# Stepper_Motor_Driver.net
KiCad netlist of a schematic drawn in EAGLE
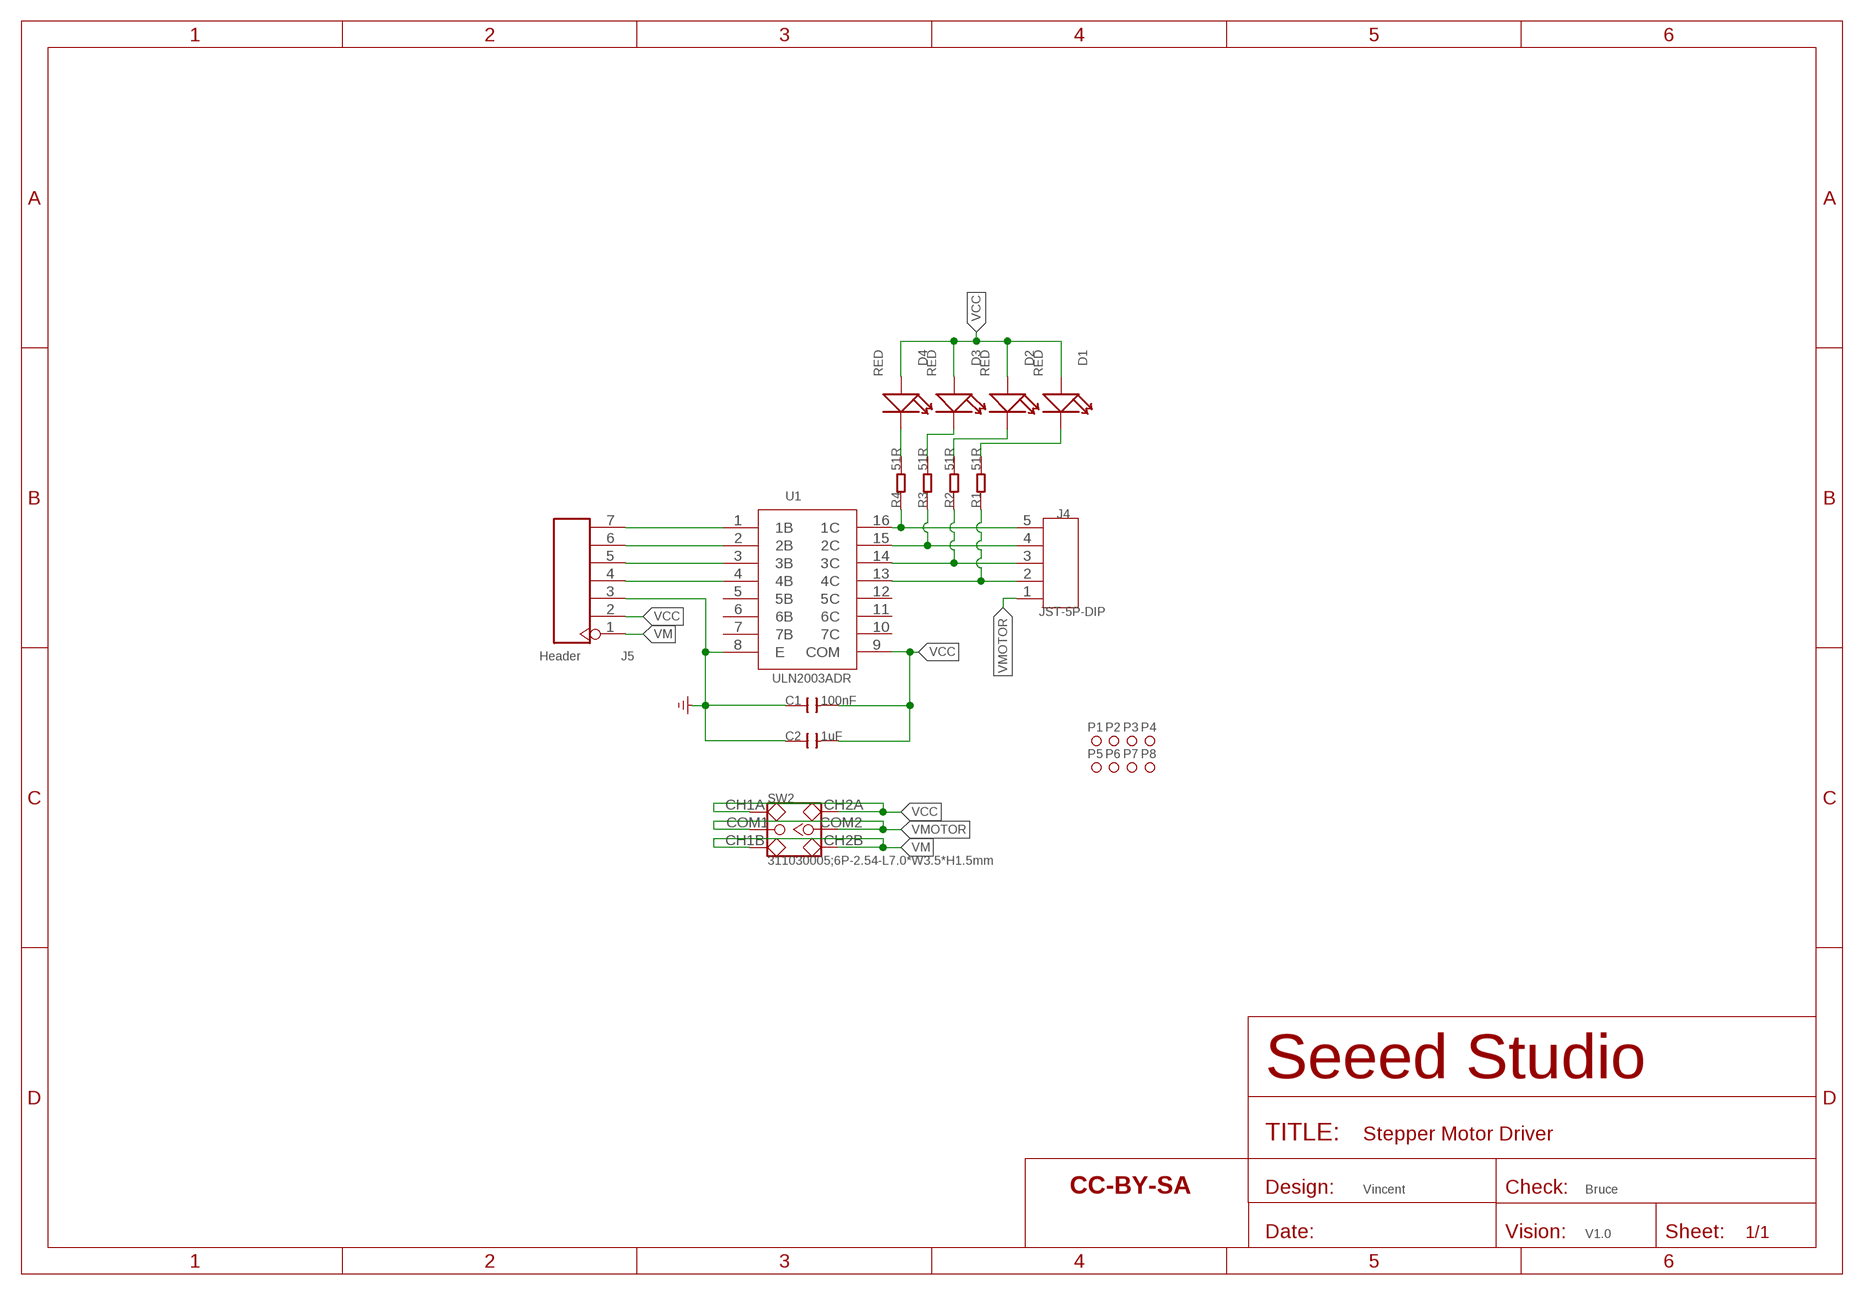
[diagram p0: schematic, sheet 1]

(export (version "E")
  (design (tool "Eeschema 10.0.6"))
  (components
    (comp (ref "C1")
      (value "100nF")
      (footprint "eagle-import:C0603")
      (libsource (lib "eagle-import") (part "CAP-0603"))
    )
    (comp (ref "C2")
      (value "1uF")
      (footprint "eagle-import:C0603")
      (libsource (lib "eagle-import") (part "CAP-0603"))
    )
    (comp (ref "D1")
      (value "RED")
      (footprint "eagle-import:LED-0603")
      (libsource (lib "eagle-import") (part "LED'0603'"))
    )
    (comp (ref "D2")
      (value "RED")
      (footprint "eagle-import:LED-0603")
      (libsource (lib "eagle-import") (part "LED'0603'"))
    )
    (comp (ref "D3")
      (value "RED")
      (footprint "eagle-import:LED-0603")
      (libsource (lib "eagle-import") (part "LED'0603'"))
    )
    (comp (ref "D4")
      (value "RED")
      (footprint "eagle-import:LED-0603")
      (libsource (lib "eagle-import") (part "LED'0603'"))
    )
    (comp (ref "J4")
      (value "JST-5P-DIP")
      (footprint "eagle-import:JST5-2.54")
      (libsource (lib "eagle-import") (part "JST-5P-DIP"))
    )
    (comp (ref "J5")
      (value "Header")
      (footprint "eagle-import:H7-2.54")
      (libsource (lib "eagle-import") (part "HEADER-7P"))
    )
    (comp (ref "P1")
      (value "MARK-1.0'ANNULAR'")
      (footprint "eagle-import:ROUND-MARK-1.0")
      (fields (field (name "PARTNO") "DNP"))
      (libsource (lib "eagle-import") (part "MARK-1.0'ANNULAR'"))
    )
    (comp (ref "P2")
      (value "MARK-1.0'ANNULAR'")
      (footprint "eagle-import:ROUND-MARK-1.0")
      (fields (field (name "PARTNO") "DNP"))
      (libsource (lib "eagle-import") (part "MARK-1.0'ANNULAR'"))
    )
    (comp (ref "P3")
      (value "MARK-1.0'ANNULAR'")
      (footprint "eagle-import:ROUND-MARK-1.0")
      (fields (field (name "PARTNO") "DNP"))
      (libsource (lib "eagle-import") (part "MARK-1.0'ANNULAR'"))
    )
    (comp (ref "P4")
      (value "MARK-1.0'ANNULAR'")
      (footprint "eagle-import:ROUND-MARK-1.0")
      (fields (field (name "PARTNO") "DNP"))
      (libsource (lib "eagle-import") (part "MARK-1.0'ANNULAR'"))
    )
    (comp (ref "P5")
      (value "MARK-1.0'ANNULAR'")
      (footprint "eagle-import:ROUND-MARK-1.0")
      (fields (field (name "PARTNO") "DNP"))
      (libsource (lib "eagle-import") (part "MARK-1.0'ANNULAR'"))
    )
    (comp (ref "P6")
      (value "MARK-1.0'ANNULAR'")
      (footprint "eagle-import:ROUND-MARK-1.0")
      (fields (field (name "PARTNO") "DNP"))
      (libsource (lib "eagle-import") (part "MARK-1.0'ANNULAR'"))
    )
    (comp (ref "P7")
      (value "MARK-1.0'ANNULAR'")
      (footprint "eagle-import:ROUND-MARK-1.0")
      (fields (field (name "PARTNO") "DNP"))
      (libsource (lib "eagle-import") (part "MARK-1.0'ANNULAR'"))
    )
    (comp (ref "P8")
      (value "MARK-1.0'ANNULAR'")
      (footprint "eagle-import:ROUND-MARK-1.0")
      (fields (field (name "PARTNO") "DNP"))
      (libsource (lib "eagle-import") (part "MARK-1.0'ANNULAR'"))
    )
    (comp (ref "R1")
      (value "51R")
      (footprint "eagle-import:R0603")
      (libsource (lib "eagle-import") (part "RES-0603"))
    )
    (comp (ref "R2")
      (value "51R")
      (footprint "eagle-import:R0603")
      (libsource (lib "eagle-import") (part "RES-0603"))
    )
    (comp (ref "R3")
      (value "51R")
      (footprint "eagle-import:R0603")
      (libsource (lib "eagle-import") (part "RES-0603"))
    )
    (comp (ref "R4")
      (value "51R")
      (footprint "eagle-import:R0603")
      (libsource (lib "eagle-import") (part "RES-0603"))
    )
    (comp (ref "SW2")
      (value "311030005;6P-2.54-L7.0*W3.5*H1.5mm")
      (footprint "eagle-import:SW6-2.54-SMD-7.0X3.5X1.5MM")
      (libsource (lib "eagle-import") (part "SWITCH-2CH-6P-SMD"))
    )
    (comp (ref "U$1")
      (value "SEEEDSTUDIO-OPEN-SCH-FRAME")
      (footprint "eagle-import:SEEEDSTUDIO-PCB-FRAME")
      (libsource (lib "eagle-import") (part "SEEEDSTUDIO-OPEN-SCH-FRAME"))
    )
    (comp (ref "U1")
      (value "ULN2003ADR")
      (footprint "eagle-import:SOIC16-1.27-10X3.9MM")
      (libsource (lib "eagle-import") (part "TRANSISTOR-ULN2003ADR"))
    )
  )
  (nets
    (net (code "1") (name "GND_POWER") (class "Default")
      (node (ref "C1") (pin "1") (pinfunction "1_1") (pintype "passive"))
      (node (ref "C2") (pin "1") (pinfunction "1_1") (pintype "passive"))
      (node (ref "J5") (pin "3") (pinfunction "3_3") (pintype "bidirectional"))
      (node (ref "U1") (pin "8") (pinfunction "E_8") (pintype "bidirectional"))
    )
    (net (code "2") (name "Net-(D1-Pad-)") (class "Default")
      (node (ref "D1") (pin "-") (pinfunction "-_-") (pintype "passive"))
      (node (ref "R1") (pin "1") (pinfunction "1_1") (pintype "passive"))
    )
    (net (code "3") (name "Net-(D2-Pad-)") (class "Default")
      (node (ref "D2") (pin "-") (pinfunction "-_-") (pintype "passive"))
      (node (ref "R2") (pin "1") (pinfunction "1_1") (pintype "passive"))
    )
    (net (code "4") (name "Net-(D3-Pad-)") (class "Default")
      (node (ref "D3") (pin "-") (pinfunction "-_-") (pintype "passive"))
      (node (ref "R3") (pin "1") (pinfunction "1_1") (pintype "passive"))
    )
    (net (code "5") (name "Net-(D4-Pad-)") (class "Default")
      (node (ref "D4") (pin "-") (pinfunction "-_-") (pintype "passive"))
      (node (ref "R4") (pin "1") (pinfunction "1_1") (pintype "passive"))
    )
    (net (code "6") (name "Net-(J4-P$2)") (class "Default")
      (node (ref "J4") (pin "2") (pinfunction "P$2_2") (pintype "bidirectional"))
      (node (ref "R1") (pin "2") (pinfunction "2_2") (pintype "passive"))
      (node (ref "U1") (pin "13") (pinfunction "4C_13") (pintype "bidirectional"))
    )
    (net (code "7") (name "Net-(J4-P$3)") (class "Default")
      (node (ref "J4") (pin "3") (pinfunction "P$3_3") (pintype "bidirectional"))
      (node (ref "R2") (pin "2") (pinfunction "2_2") (pintype "passive"))
      (node (ref "U1") (pin "14") (pinfunction "3C_14") (pintype "bidirectional"))
    )
    (net (code "8") (name "Net-(J4-P$4)") (class "Default")
      (node (ref "J4") (pin "4") (pinfunction "P$4_4") (pintype "bidirectional"))
      (node (ref "R3") (pin "2") (pinfunction "2_2") (pintype "passive"))
      (node (ref "U1") (pin "15") (pinfunction "2C_15") (pintype "bidirectional"))
    )
    (net (code "9") (name "Net-(J4-P$5)") (class "Default")
      (node (ref "J4") (pin "5") (pinfunction "P$5_5") (pintype "bidirectional"))
      (node (ref "R4") (pin "2") (pinfunction "2_2") (pintype "passive"))
      (node (ref "U1") (pin "16") (pinfunction "1C_16") (pintype "bidirectional"))
    )
    (net (code "10") (name "Net-(U1-1B)") (class "Default")
      (node (ref "J5") (pin "7") (pinfunction "7_7") (pintype "bidirectional"))
      (node (ref "U1") (pin "1") (pinfunction "1B_1") (pintype "bidirectional"))
    )
    (net (code "11") (name "Net-(U1-2B)") (class "Default")
      (node (ref "J5") (pin "6") (pinfunction "6_6") (pintype "bidirectional"))
      (node (ref "U1") (pin "2") (pinfunction "2B_2") (pintype "bidirectional"))
    )
    (net (code "12") (name "Net-(U1-3B)") (class "Default")
      (node (ref "J5") (pin "5") (pinfunction "5_5") (pintype "bidirectional"))
      (node (ref "U1") (pin "3") (pinfunction "3B_3") (pintype "bidirectional"))
    )
    (net (code "13") (name "Net-(U1-4B)") (class "Default")
      (node (ref "J5") (pin "4") (pinfunction "4_4") (pintype "bidirectional"))
      (node (ref "U1") (pin "4") (pinfunction "4B_4") (pintype "bidirectional"))
    )
    (net (code "14") (name "VCC") (class "Default")
      (node (ref "C1") (pin "2") (pinfunction "2_2") (pintype "passive"))
      (node (ref "C2") (pin "2") (pinfunction "2_2") (pintype "passive"))
      (node (ref "D1") (pin "+") (pinfunction "+_+") (pintype "passive"))
      (node (ref "D2") (pin "+") (pinfunction "+_+") (pintype "passive"))
      (node (ref "D3") (pin "+") (pinfunction "+_+") (pintype "passive"))
      (node (ref "D4") (pin "+") (pinfunction "+_+") (pintype "passive"))
      (node (ref "J5") (pin "2") (pinfunction "2_2") (pintype "bidirectional"))
      (node (ref "SW2") (pin "CH1A") (pinfunction "CH1A_CH1A") (pintype "bidirectional"))
      (node (ref "SW2") (pin "CH2A") (pinfunction "CH2A_CH2A") (pintype "bidirectional"))
      (node (ref "U1") (pin "9") (pinfunction "COM_9") (pintype "bidirectional"))
    )
    (net (code "15") (name "VM") (class "Default")
      (node (ref "J5") (pin "1") (pinfunction "1_1") (pintype "bidirectional"))
      (node (ref "SW2") (pin "CH1B") (pinfunction "CH1B_CH1B") (pintype "bidirectional"))
      (node (ref "SW2") (pin "CH2B") (pinfunction "CH2B_CH2B") (pintype "bidirectional"))
    )
    (net (code "16") (name "VMOTOR") (class "Default")
      (node (ref "J4") (pin "1") (pinfunction "P$1_1") (pintype "bidirectional"))
      (node (ref "SW2") (pin "COM1") (pinfunction "COM1_COM1") (pintype "bidirectional"))
      (node (ref "SW2") (pin "COM2") (pinfunction "COM2_COM2") (pintype "bidirectional"))
    )
    (net (code "17") (name "unconnected-(U1-5B-Pad5)") (class "Default")
      (node (ref "U1") (pin "5") (pinfunction "5B_5") (pintype "bidirectional"))
    )
    (net (code "18") (name "unconnected-(U1-5C-Pad12)") (class "Default")
      (node (ref "U1") (pin "12") (pinfunction "5C_12") (pintype "bidirectional"))
    )
    (net (code "19") (name "unconnected-(U1-6B-Pad6)") (class "Default")
      (node (ref "U1") (pin "6") (pinfunction "6B_6") (pintype "bidirectional"))
    )
    (net (code "20") (name "unconnected-(U1-6C-Pad11)") (class "Default")
      (node (ref "U1") (pin "11") (pinfunction "6C_11") (pintype "bidirectional"))
    )
    (net (code "21") (name "unconnected-(U1-7B-Pad7)") (class "Default")
      (node (ref "U1") (pin "7") (pinfunction "7B_7") (pintype "bidirectional"))
    )
    (net (code "22") (name "unconnected-(U1-7C-Pad10)") (class "Default")
      (node (ref "U1") (pin "10") (pinfunction "7C_10") (pintype "bidirectional"))
    )
  )
)
